# PWM_Controller_Half_Bridge_IR2110.net
KiCad netlist of a schematic drawn in Altium Designer
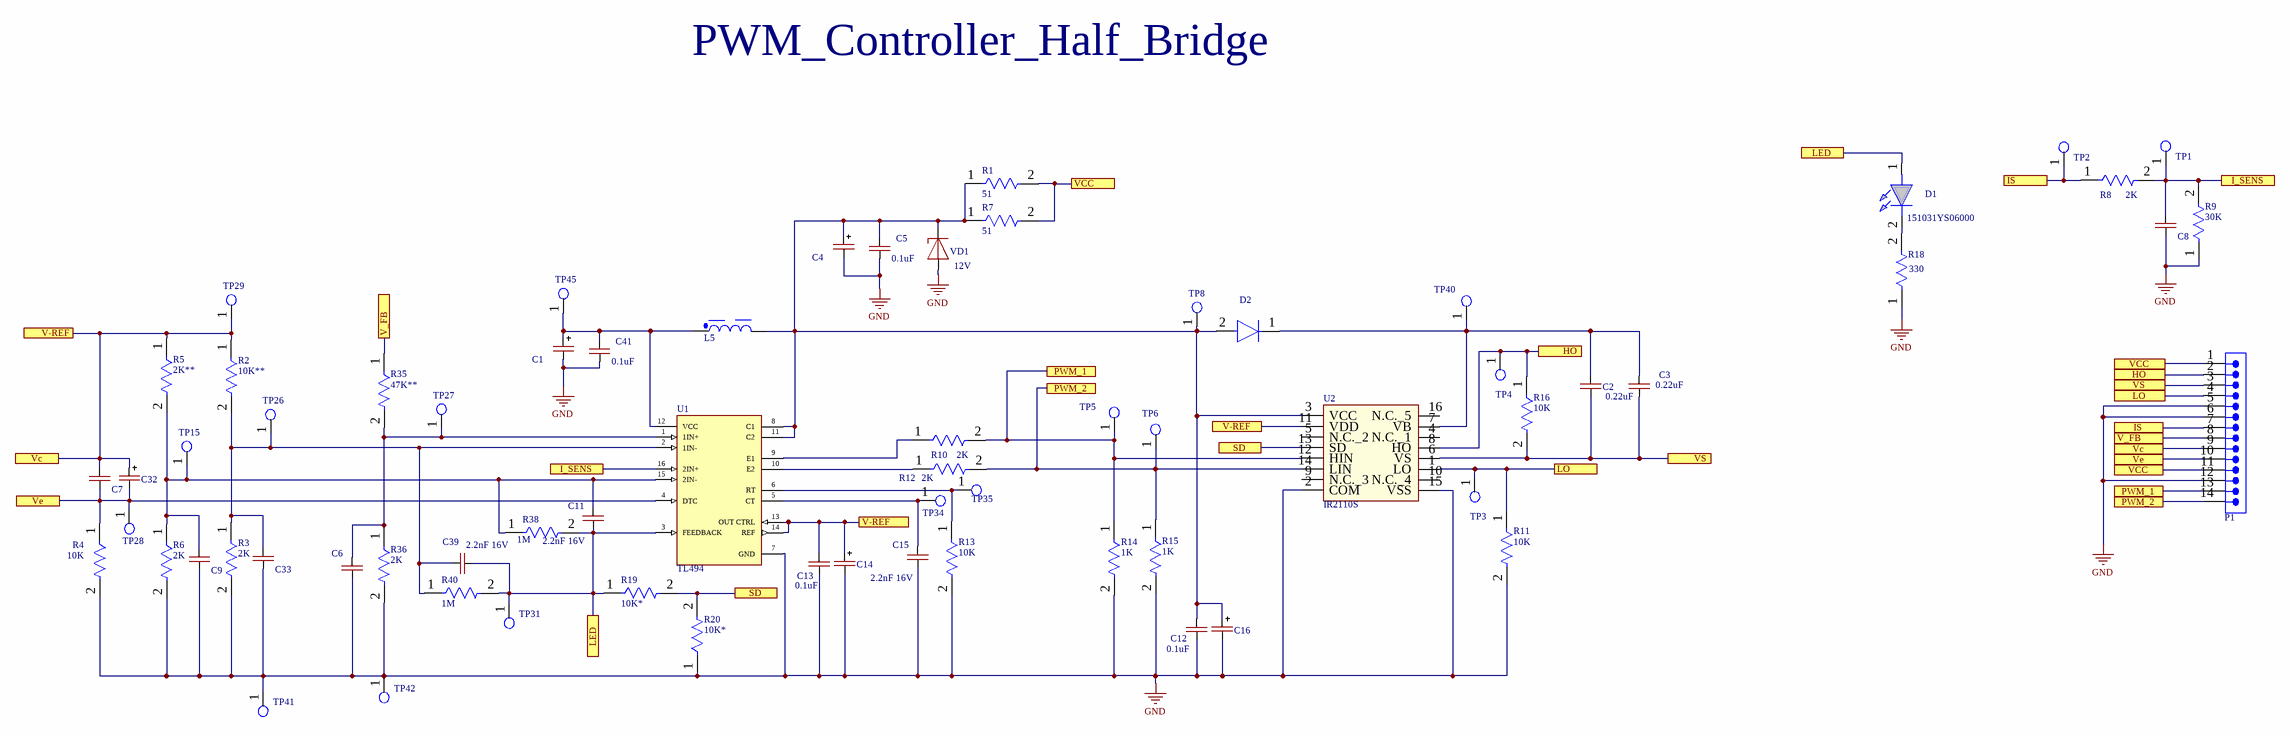
[diagram p0: PWM_Controller_Half_Bridge_IR2110.SchDoc]

(export (version "E")
  (design (tool "Eeschema 10.0.6"))
  (components
    (comp (ref "C1")
      (value "CAP-POLAR")
      (footprint "SIZE_EEE")
      (libsource (lib "PASSIVE_COMPONENTS") (part "CAP-POLAR"))
    )
    (comp (ref "C2")
      (value "0.22uF")
      (footprint "FP-C1210X475K5RACTU-IPC_C")
      (libsource (lib "PASSIVE_COMPONENTS") (part "CAP_1210"))
    )
    (comp (ref "C3")
      (value "0.22uF")
      (footprint "FP-C1210X475K5RACTU-IPC_C")
      (libsource (lib "PASSIVE_COMPONENTS") (part "CAP_1210"))
    )
    (comp (ref "C4")
      (value "CAP-POLAR")
      (footprint "SIZE_EEE")
      (libsource (lib "PASSIVE_COMPONENTS") (part "CAP-POLAR"))
    )
    (comp (ref "C5")
      (value "0.1uF")
      (footprint "CAP-0805")
      (libsource (lib "PASSIVE_COMPONENTS") (part "CAP-NON-POLAR"))
    )
    (comp (ref "C6")
      (value "CAP-NON-POLAR")
      (footprint "CAP-0805")
      (libsource (lib "PASSIVE_COMPONENTS") (part "CAP-NON-POLAR"))
    )
    (comp (ref "C7")
      (value "CAP-NON-POLAR")
      (footprint "CAP-0805")
      (libsource (lib "PASSIVE_COMPONENTS") (part "CAP-NON-POLAR"))
    )
    (comp (ref "C8")
      (value "CAP-NON-POLAR")
      (footprint "CAP-0805")
      (libsource (lib "PASSIVE_COMPONENTS") (part "CAP-NON-POLAR"))
    )
    (comp (ref "C9")
      (value "CAP-NON-POLAR")
      (footprint "CAP-0805")
      (libsource (lib "PASSIVE_COMPONENTS") (part "CAP-NON-POLAR"))
    )
    (comp (ref "C11")
      (value "2.2nF 16V")
      (footprint "CAP-0805")
      (libsource (lib "PASSIVE_COMPONENTS") (part "CAP-NON-POLAR"))
    )
    (comp (ref "C12")
      (value "0.1uF")
      (footprint "CAP-0805")
      (libsource (lib "PASSIVE_COMPONENTS") (part "CAP-NON-POLAR"))
    )
    (comp (ref "C13")
      (value "0.1uF")
      (footprint "CAP-0805")
      (libsource (lib "PASSIVE_COMPONENTS") (part "CAP-NON-POLAR"))
    )
    (comp (ref "C14")
      (value "CAP-POLAR")
      (footprint "CAP-TAN-D")
      (libsource (lib "PASSIVE_COMPONENTS") (part "CAP-POLAR"))
    )
    (comp (ref "C15")
      (value "2.2nF 16V")
      (footprint "CAP-0805")
      (libsource (lib "PASSIVE_COMPONENTS") (part "CAP-NON-POLAR"))
    )
    (comp (ref "C16")
      (value "CAP-POLAR")
      (footprint "CAP-TAN-D")
      (libsource (lib "PASSIVE_COMPONENTS") (part "CAP-POLAR"))
    )
    (comp (ref "C32")
      (value "CAP-POLAR")
      (footprint "CAP-TAN-D")
      (libsource (lib "PASSIVE_COMPONENTS") (part "CAP-POLAR"))
    )
    (comp (ref "C33")
      (value "CAP-NON-POLAR")
      (footprint "CAP-0805")
      (libsource (lib "PASSIVE_COMPONENTS") (part "CAP-NON-POLAR"))
    )
    (comp (ref "C39")
      (value "2.2nF 16V")
      (footprint "CAP-0805")
      (libsource (lib "PASSIVE_COMPONENTS") (part "CAP-NON-POLAR"))
    )
    (comp (ref "C41")
      (value "0.1uF")
      (footprint "CAP-0805")
      (libsource (lib "PASSIVE_COMPONENTS") (part "CAP-NON-POLAR"))
    )
    (comp (ref "D1")
      (value "151031YS06000")
      (footprint "LED_RED")
      (description "WURTH ELEKTRONIK - 151031YS06000 - LED, Yellow, Through Hole, T-1 (3mm), 30 mA, 2 V, 590 nm")
      (fields (field (name "MOUSER PART NUMBER") "710-151031YS06000"))
      (libsource (lib "Optic-LED") (part "LED"))
    )
    (comp (ref "D2") (value "US1G") (footprint "DO-214AA") (libsource (lib "Diodes") (part "US1G")))
    (comp (ref "L5")
      (value "47µH, 1.17A")
      (footprint "WE-PD2_7850")
      (description "WE-PD2 SMT Power Inductor, size 7850, 47µH, 1.17A, 0.18Ω")
      (fields
        (field (name "MANUFACTURER PART NUMBER") "744775147")
        (field (name "MANUFACTURER") "Wurth Elektronik")
      )
      (libsource (lib "WE-PD2 (rev22d)") (part "744775147"))
    )
    (comp (ref "P1")
      (value "61301411021")
      (footprint "61301411021")
      (description "WR-PHD Pin Header, THT, Angled, pitch 2.54mm, 1 Row, 14P")
      (fields (field (name "MANUFACTURER") "Wurth Elektronik"))
      (libsource (lib "Altium_WR-PHD (rev22b)") (part "61301411021"))
    )
    (comp (ref "R1")
      (value "51")
      (footprint "FP-RMCF1210-MFG")
      (description "51Ω ±5% 0.5W 1210 Thick Film Chip Resistor AEC-Q200 compliant")
      (fields (field (name "TOLERANCE") "5%"))
      (libsource (lib "Altium Content Vault") (part "1029c3af85768c4190bb7ad29bc67b5"))
    )
    (comp (ref "R2")
      (value "10K**")
      (footprint "RES-0805")
      (description "10K")
      (libsource (lib "PASSIVE_COMPONENTS") (part "RES-CONST"))
    )
    (comp (ref "R3")
      (value "2K")
      (footprint "RES-0805")
      (libsource (lib "PASSIVE_COMPONENTS") (part "RES-CONST"))
    )
    (comp (ref "R4")
      (value "10K")
      (footprint "RES-0805")
      (libsource (lib "PASSIVE_COMPONENTS") (part "RES-CONST"))
    )
    (comp (ref "R5")
      (value "2K**")
      (footprint "RES-0805")
      (description "2K")
      (libsource (lib "PASSIVE_COMPONENTS") (part "RES-CONST"))
    )
    (comp (ref "R6")
      (value "2K")
      (footprint "RES-0805")
      (libsource (lib "PASSIVE_COMPONENTS") (part "RES-CONST"))
    )
    (comp (ref "R7")
      (value "51")
      (footprint "FP-RMCF1210-MFG")
      (description "51Ω ±5% 0.5W 1210 Thick Film Chip Resistor AEC-Q200 compliant")
      (fields (field (name "TOLERANCE") "5%"))
      (libsource (lib "Altium Content Vault") (part "1029c3af85768c4190bb7ad29bc67b5"))
    )
    (comp (ref "R8")
      (value "2K")
      (footprint "RES-0805")
      (libsource (lib "PASSIVE_COMPONENTS") (part "RES-CONST"))
    )
    (comp (ref "R9")
      (value "30K")
      (footprint "RES-0805")
      (libsource (lib "PASSIVE_COMPONENTS") (part "RES-CONST"))
    )
    (comp (ref "R10")
      (value "2K")
      (footprint "RES-0805")
      (libsource (lib "PASSIVE_COMPONENTS") (part "RES-CONST"))
    )
    (comp (ref "R11")
      (value "10K")
      (footprint "RES-0805")
      (libsource (lib "PASSIVE_COMPONENTS") (part "RES-CONST"))
    )
    (comp (ref "R12")
      (value "2K")
      (footprint "RES-0805")
      (libsource (lib "PASSIVE_COMPONENTS") (part "RES-CONST"))
    )
    (comp (ref "R13")
      (value "10K")
      (footprint "RES-0805")
      (libsource (lib "PASSIVE_COMPONENTS") (part "RES-CONST"))
    )
    (comp (ref "R14")
      (value "1K")
      (footprint "RES-0805")
      (libsource (lib "PASSIVE_COMPONENTS") (part "RES-CONST"))
    )
    (comp (ref "R15")
      (value "1K")
      (footprint "RES-0805")
      (libsource (lib "PASSIVE_COMPONENTS") (part "RES-CONST"))
    )
    (comp (ref "R16")
      (value "10K")
      (footprint "RES-0805")
      (libsource (lib "PASSIVE_COMPONENTS") (part "RES-CONST"))
    )
    (comp (ref "R18")
      (value "330")
      (footprint "RES-0805")
      (libsource (lib "PASSIVE_COMPONENTS") (part "RES-CONST"))
    )
    (comp (ref "R19")
      (value "10K*")
      (footprint "RES-0805")
      (description "10K")
      (libsource (lib "PASSIVE_COMPONENTS") (part "RES-CONST"))
    )
    (comp (ref "R20")
      (value "10K*")
      (footprint "RES-0805")
      (description "10K")
      (libsource (lib "PASSIVE_COMPONENTS") (part "RES-CONST"))
    )
    (comp (ref "R35")
      (value "47K**")
      (footprint "RES-0805")
      (description "47K")
      (libsource (lib "PASSIVE_COMPONENTS") (part "RES-CONST"))
    )
    (comp (ref "R36")
      (value "2K")
      (footprint "RES-0805")
      (libsource (lib "PASSIVE_COMPONENTS") (part "RES-CONST"))
    )
    (comp (ref "R38")
      (value "1M")
      (footprint "RES-0805")
      (libsource (lib "PASSIVE_COMPONENTS") (part "RES-CONST"))
    )
    (comp (ref "R40")
      (value "1M")
      (footprint "RES-0805")
      (libsource (lib "PASSIVE_COMPONENTS") (part "RES-CONST"))
    )
    (comp (ref "TP1")
      (value "~")
      (footprint "Test_Point")
      (description "Test_Point")
      (libsource (lib "Connectors") (part "TP_PCB?"))
    )
    (comp (ref "TP2")
      (value "~")
      (footprint "Test_Point")
      (description "Test_Point")
      (libsource (lib "Connectors") (part "TP_PCB?"))
    )
    (comp (ref "TP3")
      (value "~")
      (footprint "Test_Point")
      (description "Test_Point")
      (libsource (lib "Connectors") (part "TP_PCB?"))
    )
    (comp (ref "TP4")
      (value "~")
      (footprint "Test_Point")
      (description "Test_Point")
      (libsource (lib "Connectors") (part "TP_PCB?"))
    )
    (comp (ref "TP5")
      (value "~")
      (footprint "Test_Point")
      (description "Test_Point")
      (libsource (lib "Connectors") (part "TP_PCB?"))
    )
    (comp (ref "TP6")
      (value "~")
      (footprint "Test_Point")
      (description "Test_Point")
      (libsource (lib "Connectors") (part "TP_PCB?"))
    )
    (comp (ref "TP8")
      (value "~")
      (footprint "Test_Point")
      (description "Test_Point")
      (libsource (lib "Connectors") (part "TP_PCB?"))
    )
    (comp (ref "TP15")
      (value "~")
      (footprint "Test_Point")
      (description "Test_Point")
      (libsource (lib "Connectors") (part "TP_PCB?"))
    )
    (comp (ref "TP26")
      (value "~")
      (footprint "Test_Point")
      (description "Test_Point")
      (libsource (lib "Connectors") (part "TP_PCB?"))
    )
    (comp (ref "TP27")
      (value "~")
      (footprint "Test_Point")
      (description "Test_Point")
      (libsource (lib "Connectors") (part "TP_PCB?"))
    )
    (comp (ref "TP28")
      (value "~")
      (footprint "Test_Point")
      (description "Test_Point")
      (libsource (lib "Connectors") (part "TP_PCB?"))
    )
    (comp (ref "TP29")
      (value "~")
      (footprint "Test_Point")
      (description "Test_Point")
      (libsource (lib "Connectors") (part "TP_PCB?"))
    )
    (comp (ref "TP31")
      (value "~")
      (footprint "Test_Point")
      (description "Test_Point")
      (libsource (lib "Connectors") (part "TP_PCB?"))
    )
    (comp (ref "TP34")
      (value "~")
      (footprint "Test_Point")
      (description "Test_Point")
      (libsource (lib "Connectors") (part "TP_PCB?"))
    )
    (comp (ref "TP35")
      (value "~")
      (footprint "Test_Point")
      (description "Test_Point")
      (libsource (lib "Connectors") (part "TP_PCB?"))
    )
    (comp (ref "TP40")
      (value "~")
      (footprint "Test_Point")
      (description "Test_Point")
      (libsource (lib "Connectors") (part "TP_PCB?"))
    )
    (comp (ref "TP41")
      (value "~")
      (footprint "Test_Point")
      (description "Test_Point")
      (libsource (lib "Connectors") (part "TP_PCB?"))
    )
    (comp (ref "TP42")
      (value "~")
      (footprint "Test_Point")
      (description "Test_Point")
      (libsource (lib "Connectors") (part "TP_PCB?"))
    )
    (comp (ref "TP45")
      (value "~")
      (footprint "Test_Point")
      (description "Test_Point")
      (libsource (lib "Connectors") (part "TP_PCB?"))
    )
    (comp (ref "U1")
      (value "TL494")
      (footprint "SOIC-16-M")
      (description "TL494 Pwm controller")
      (libsource (lib "Integrated_Circuts") (part "TL494"))
    )
    (comp (ref "U2")
      (value "IR2110S")
      (footprint "SOIC127P1036X391-16N")
      (description "IC DRIVER HIGH/LOW SIDE 16-SOIC")
      (libsource (lib "Integrated_Circuts") (part "IR2110S"))
    )
    (comp (ref "VD1") (value "12V") (footprint "DO-017AA") (libsource (lib "Diodes") (part "ZENER")))
  )
  (nets
    (net (code "1") (name "/HO") (class "Default")
      (node (ref "P1") (pin "2") (pinfunction "2_2") (pintype "passive"))
      (node (ref "R16") (pin "1") (pinfunction "1_1") (pintype "passive"))
      (node (ref "TP4") (pin "1") (pinfunction "G9_1") (pintype "passive"))
      (node (ref "U2") (pin "8") (pinfunction "HO_8") (pintype "passive"))
    )
    (net (code "2") (name "/IS") (class "Default")
      (node (ref "P1") (pin "7") (pinfunction "7_7") (pintype "passive"))
      (node (ref "R8") (pin "1") (pinfunction "1_1") (pintype "passive"))
      (node (ref "TP2") (pin "1") (pinfunction "G9_1") (pintype "passive"))
    )
    (net (code "3") (name "/I_SENS") (class "Default")
      (node (ref "C8") (pin "2") (pinfunction "2_2") (pintype "passive"))
      (node (ref "R8") (pin "2") (pinfunction "2_2") (pintype "passive"))
      (node (ref "R9") (pin "2") (pinfunction "2_2") (pintype "passive"))
      (node (ref "TP1") (pin "1") (pinfunction "G9_1") (pintype "passive"))
      (node (ref "U1") (pin "16") (pinfunction "2IN+_16") (pintype "input"))
    )
    (net (code "4") (name "/LED") (class "Default")
      (node (ref "C11") (pin "1") (pinfunction "1_1") (pintype "passive"))
      (node (ref "C39") (pin "1") (pinfunction "1_1") (pintype "passive"))
      (node (ref "D1") (pin "1") (pinfunction "A_1") (pintype "passive"))
      (node (ref "R19") (pin "1") (pinfunction "1_1") (pintype "passive"))
      (node (ref "R38") (pin "2") (pinfunction "2_2") (pintype "passive"))
      (node (ref "R40") (pin "2") (pinfunction "2_2") (pintype "passive"))
      (node (ref "TP31") (pin "1") (pinfunction "G9_1") (pintype "passive"))
      (node (ref "U1") (pin "3") (pinfunction "FEEDBACK_3") (pintype "input"))
    )
    (net (code "5") (name "/LO") (class "Default")
      (node (ref "P1") (pin "4") (pinfunction "4_4") (pintype "passive"))
      (node (ref "R11") (pin "1") (pinfunction "1_1") (pintype "passive"))
      (node (ref "TP3") (pin "1") (pinfunction "G9_1") (pintype "passive"))
      (node (ref "U2") (pin "1") (pinfunction "LO_1") (pintype "passive"))
    )
    (net (code "6") (name "/PWM_1") (class "Default")
      (node (ref "P1") (pin "13") (pinfunction "13_13") (pintype "passive"))
      (node (ref "R10") (pin "2") (pinfunction "2_2") (pintype "passive"))
      (node (ref "R14") (pin "1") (pinfunction "1_1") (pintype "passive"))
      (node (ref "TP5") (pin "1") (pinfunction "G9_1") (pintype "passive"))
      (node (ref "U2") (pin "12") (pinfunction "HIN_12") (pintype "passive"))
    )
    (net (code "7") (name "/PWM_2") (class "Default")
      (node (ref "P1") (pin "14") (pinfunction "14_14") (pintype "passive"))
      (node (ref "R12") (pin "2") (pinfunction "2_2") (pintype "passive"))
      (node (ref "R15") (pin "1") (pinfunction "1_1") (pintype "passive"))
      (node (ref "TP6") (pin "1") (pinfunction "G9_1") (pintype "passive"))
      (node (ref "U2") (pin "14") (pinfunction "LIN_14") (pintype "passive"))
    )
    (net (code "8") (name "/SD") (class "Default")
      (node (ref "R19") (pin "2") (pinfunction "2_2") (pintype "passive"))
      (node (ref "R20") (pin "2") (pinfunction "2_2") (pintype "passive"))
      (node (ref "U2") (pin "13") (pinfunction "SD_13") (pintype "passive"))
    )
    (net (code "9") (name "/V-REF") (class "Default")
      (node (ref "C13") (pin "2") (pinfunction "2_2") (pintype "passive"))
      (node (ref "C14") (pin "1") (pinfunction "+_1") (pintype "passive"))
      (node (ref "C32") (pin "1") (pinfunction "+_1") (pintype "passive"))
      (node (ref "C7") (pin "2") (pinfunction "2_2") (pintype "passive"))
      (node (ref "P1") (pin "9") (pinfunction "9_9") (pintype "passive"))
      (node (ref "R2") (pin "1") (pinfunction "1_1") (pintype "passive"))
      (node (ref "R5") (pin "1") (pinfunction "1_1") (pintype "passive"))
      (node (ref "TP29") (pin "1") (pinfunction "G9_1") (pintype "passive"))
      (node (ref "U1") (pin "13") (pinfunction "OUT_CTRL_13") (pintype "input"))
      (node (ref "U1") (pin "14") (pinfunction "REF_14") (pintype "output"))
      (node (ref "U2") (pin "11") (pinfunction "VDD_11") (pintype "passive"))
    )
    (net (code "10") (name "/VCC") (class "Default")
      (node (ref "P1") (pin "1") (pinfunction "1_1") (pintype "passive"))
      (node (ref "P1") (pin "11") (pinfunction "11_11") (pintype "passive"))
      (node (ref "R1") (pin "2") (pinfunction "2_2") (pintype "passive"))
      (node (ref "R7") (pin "2") (pinfunction "2_2") (pintype "passive"))
    )
    (net (code "11") (name "/VS") (class "Default")
      (node (ref "C2") (pin "1") (pinfunction "1_1") (pintype "passive"))
      (node (ref "C3") (pin "1") (pinfunction "1_1") (pintype "passive"))
      (node (ref "P1") (pin "3") (pinfunction "3_3") (pintype "passive"))
      (node (ref "R16") (pin "2") (pinfunction "2_2") (pintype "passive"))
      (node (ref "U2") (pin "6") (pinfunction "VS_6") (pintype "passive"))
    )
    (net (code "12") (name "/V_FB") (class "Default")
      (node (ref "P1") (pin "8") (pinfunction "8_8") (pintype "passive"))
      (node (ref "R35") (pin "1") (pinfunction "1_1") (pintype "passive"))
    )
    (net (code "13") (name "/Ve") (class "Default")
      (node (ref "C32") (pin "2") (pinfunction "-_2") (pintype "passive"))
      (node (ref "C7") (pin "1") (pinfunction "1_1") (pintype "passive"))
      (node (ref "P1") (pin "10") (pinfunction "10_10") (pintype "passive"))
      (node (ref "R4") (pin "1") (pinfunction "1_1") (pintype "passive"))
      (node (ref "TP28") (pin "1") (pinfunction "G9_1") (pintype "passive"))
      (node (ref "U1") (pin "4") (pinfunction "DTC_4") (pintype "input"))
    )
    (net (code "14") (name "GND") (class "Default")
      (node (ref "C1") (pin "2") (pinfunction "-_2") (pintype "passive"))
      (node (ref "C12") (pin "1") (pinfunction "1_1") (pintype "passive"))
      (node (ref "C13") (pin "1") (pinfunction "1_1") (pintype "passive"))
      (node (ref "C14") (pin "2") (pinfunction "-_2") (pintype "passive"))
      (node (ref "C15") (pin "1") (pinfunction "1_1") (pintype "passive"))
      (node (ref "C16") (pin "2") (pinfunction "-_2") (pintype "passive"))
      (node (ref "C33") (pin "1") (pinfunction "1_1") (pintype "passive"))
      (node (ref "C4") (pin "2") (pinfunction "-_2") (pintype "passive"))
      (node (ref "C41") (pin "1") (pinfunction "1_1") (pintype "passive"))
      (node (ref "C5") (pin "1") (pinfunction "1_1") (pintype "passive"))
      (node (ref "C6") (pin "1") (pinfunction "1_1") (pintype "passive"))
      (node (ref "C8") (pin "1") (pinfunction "1_1") (pintype "passive"))
      (node (ref "C9") (pin "1") (pinfunction "1_1") (pintype "passive"))
      (node (ref "P1") (pin "12") (pinfunction "12_12") (pintype "passive"))
      (node (ref "P1") (pin "5") (pinfunction "5_5") (pintype "passive"))
      (node (ref "P1") (pin "6") (pinfunction "6_6") (pintype "passive"))
      (node (ref "R11") (pin "2") (pinfunction "2_2") (pintype "passive"))
      (node (ref "R13") (pin "2") (pinfunction "2_2") (pintype "passive"))
      (node (ref "R14") (pin "2") (pinfunction "2_2") (pintype "passive"))
      (node (ref "R15") (pin "2") (pinfunction "2_2") (pintype "passive"))
      (node (ref "R18") (pin "1") (pinfunction "1_1") (pintype "passive"))
      (node (ref "R20") (pin "1") (pinfunction "1_1") (pintype "passive"))
      (node (ref "R3") (pin "2") (pinfunction "2_2") (pintype "passive"))
      (node (ref "R36") (pin "2") (pinfunction "2_2") (pintype "passive"))
      (node (ref "R4") (pin "2") (pinfunction "2_2") (pintype "passive"))
      (node (ref "R6") (pin "2") (pinfunction "2_2") (pintype "passive"))
      (node (ref "R9") (pin "1") (pinfunction "1_1") (pintype "passive"))
      (node (ref "TP41") (pin "1") (pinfunction "G9_1") (pintype "passive"))
      (node (ref "TP42") (pin "1") (pinfunction "G9_1") (pintype "passive"))
      (node (ref "U1") (pin "7") (pinfunction "GND_7") (pintype "power_in"))
      (node (ref "U2") (pin "15") (pinfunction "VSS_15") (pintype "passive"))
      (node (ref "U2") (pin "2") (pinfunction "COM_2") (pintype "passive"))
      (node (ref "VD1") (pin "2") (pinfunction "A_2") (pintype "passive"))
    )
    (net (code "15") (name "Net-(C1-+)") (class "Default")
      (node (ref "C1") (pin "1") (pinfunction "+_1") (pintype "passive"))
      (node (ref "C41") (pin "2") (pinfunction "2_2") (pintype "passive"))
      (node (ref "L5") (pin "1") (pinfunction "1_1") (pintype "passive"))
      (node (ref "TP45") (pin "1") (pinfunction "G9_1") (pintype "passive"))
      (node (ref "U1") (pin "12") (pinfunction "VCC_12") (pintype "power_in"))
    )
    (net (code "16") (name "Net-(C16-+)") (class "Default")
      (node (ref "C12") (pin "2") (pinfunction "2_2") (pintype "passive"))
      (node (ref "C16") (pin "1") (pinfunction "+_1") (pintype "passive"))
      (node (ref "C4") (pin "1") (pinfunction "+_1") (pintype "passive"))
      (node (ref "C5") (pin "2") (pinfunction "2_2") (pintype "passive"))
      (node (ref "D2") (pin "2") (pinfunction "A_2") (pintype "passive"))
      (node (ref "L5") (pin "2") (pinfunction "2_2") (pintype "passive"))
      (node (ref "R1") (pin "1") (pinfunction "1_1") (pintype "passive"))
      (node (ref "R7") (pin "1") (pinfunction "1_1") (pintype "passive"))
      (node (ref "TP8") (pin "1") (pinfunction "G9_1") (pintype "passive"))
      (node (ref "U1") (pin "11") (pinfunction "C2_11") (pintype "passive"))
      (node (ref "U1") (pin "8") (pinfunction "C1_8") (pintype "passive"))
      (node (ref "U2") (pin "3") (pinfunction "VCC_3") (pintype "passive"))
      (node (ref "VD1") (pin "1") (pinfunction "C_1") (pintype "passive"))
    )
    (net (code "17") (name "Net-(D1-K)") (class "Default")
      (node (ref "D1") (pin "2") (pinfunction "K_2") (pintype "passive"))
      (node (ref "R18") (pin "2") (pinfunction "2_2") (pintype "passive"))
    )
    (net (code "18") (name "Net-(D2-C)") (class "Default")
      (node (ref "C2") (pin "2") (pinfunction "2_2") (pintype "passive"))
      (node (ref "C3") (pin "2") (pinfunction "2_2") (pintype "passive"))
      (node (ref "D2") (pin "1") (pinfunction "C_1") (pintype "passive"))
      (node (ref "TP40") (pin "1") (pinfunction "G9_1") (pintype "passive"))
      (node (ref "U2") (pin "7") (pinfunction "VB_7") (pintype "passive"))
    )
    (net (code "19") (name "Net-(TP15-G9)") (class "Default")
      (node (ref "C11") (pin "2") (pinfunction "2_2") (pintype "passive"))
      (node (ref "C9") (pin "2") (pinfunction "2_2") (pintype "passive"))
      (node (ref "R38") (pin "1") (pinfunction "1_1") (pintype "passive"))
      (node (ref "R5") (pin "2") (pinfunction "2_2") (pintype "passive"))
      (node (ref "R6") (pin "1") (pinfunction "1_1") (pintype "passive"))
      (node (ref "TP15") (pin "1") (pinfunction "G9_1") (pintype "passive"))
      (node (ref "U1") (pin "15") (pinfunction "2IN-_15") (pintype "input"))
    )
    (net (code "20") (name "Net-(TP26-G9)") (class "Default")
      (node (ref "C33") (pin "2") (pinfunction "2_2") (pintype "passive"))
      (node (ref "C39") (pin "2") (pinfunction "2_2") (pintype "passive"))
      (node (ref "R2") (pin "2") (pinfunction "2_2") (pintype "passive"))
      (node (ref "R3") (pin "1") (pinfunction "1_1") (pintype "passive"))
      (node (ref "R40") (pin "1") (pinfunction "1_1") (pintype "passive"))
      (node (ref "TP26") (pin "1") (pinfunction "G9_1") (pintype "passive"))
      (node (ref "U1") (pin "2") (pinfunction "1IN-_2") (pintype "input"))
    )
    (net (code "21") (name "Net-(TP27-G9)") (class "Default")
      (node (ref "C6") (pin "2") (pinfunction "2_2") (pintype "passive"))
      (node (ref "R35") (pin "2") (pinfunction "2_2") (pintype "passive"))
      (node (ref "R36") (pin "1") (pinfunction "1_1") (pintype "passive"))
      (node (ref "TP27") (pin "1") (pinfunction "G9_1") (pintype "passive"))
      (node (ref "U1") (pin "1") (pinfunction "1IN+_1") (pintype "input"))
    )
    (net (code "22") (name "Net-(TP34-G9)") (class "Default")
      (node (ref "C15") (pin "2") (pinfunction "2_2") (pintype "passive"))
      (node (ref "TP34") (pin "1") (pinfunction "G9_1") (pintype "passive"))
      (node (ref "U1") (pin "5") (pinfunction "CT_5") (pintype "passive"))
    )
    (net (code "23") (name "Net-(TP35-G9)") (class "Default")
      (node (ref "R13") (pin "1") (pinfunction "1_1") (pintype "passive"))
      (node (ref "TP35") (pin "1") (pinfunction "G9_1") (pintype "passive"))
      (node (ref "U1") (pin "6") (pinfunction "RT_6") (pintype "passive"))
    )
    (net (code "24") (name "Net-(U1-E1)") (class "Default")
      (node (ref "R10") (pin "1") (pinfunction "1_1") (pintype "passive"))
      (node (ref "U1") (pin "9") (pinfunction "E1_9") (pintype "passive"))
    )
    (net (code "25") (name "Net-(U1-E2)") (class "Default")
      (node (ref "R12") (pin "1") (pinfunction "1_1") (pintype "passive"))
      (node (ref "U1") (pin "10") (pinfunction "E2_10") (pintype "passive"))
    )
    (net (code "26") (name "unconnected-(U2-N.C._1-Pad4)") (class "Default")
      (node (ref "U2") (pin "4") (pinfunction "N.C._1_4") (pintype "passive"))
    )
    (net (code "27") (name "unconnected-(U2-N.C._2-Pad5)") (class "Default")
      (node (ref "U2") (pin "5") (pinfunction "N.C._2_5") (pintype "passive"))
    )
    (net (code "28") (name "unconnected-(U2-N.C._3-Pad9)") (class "Default")
      (node (ref "U2") (pin "9") (pinfunction "N.C._3_9") (pintype "passive"))
    )
    (net (code "29") (name "unconnected-(U2-N.C._4-Pad10)") (class "Default")
      (node (ref "U2") (pin "10") (pinfunction "N.C._4_10") (pintype "passive"))
    )
    (net (code "30") (name "unconnected-(U2-N.C._5-Pad16)") (class "Default")
      (node (ref "U2") (pin "16") (pinfunction "N.C._5_16") (pintype "passive"))
    )
  )
)
